# CorrienteTestMaquina.net
KiCad netlist of a schematic drawn in EAGLE
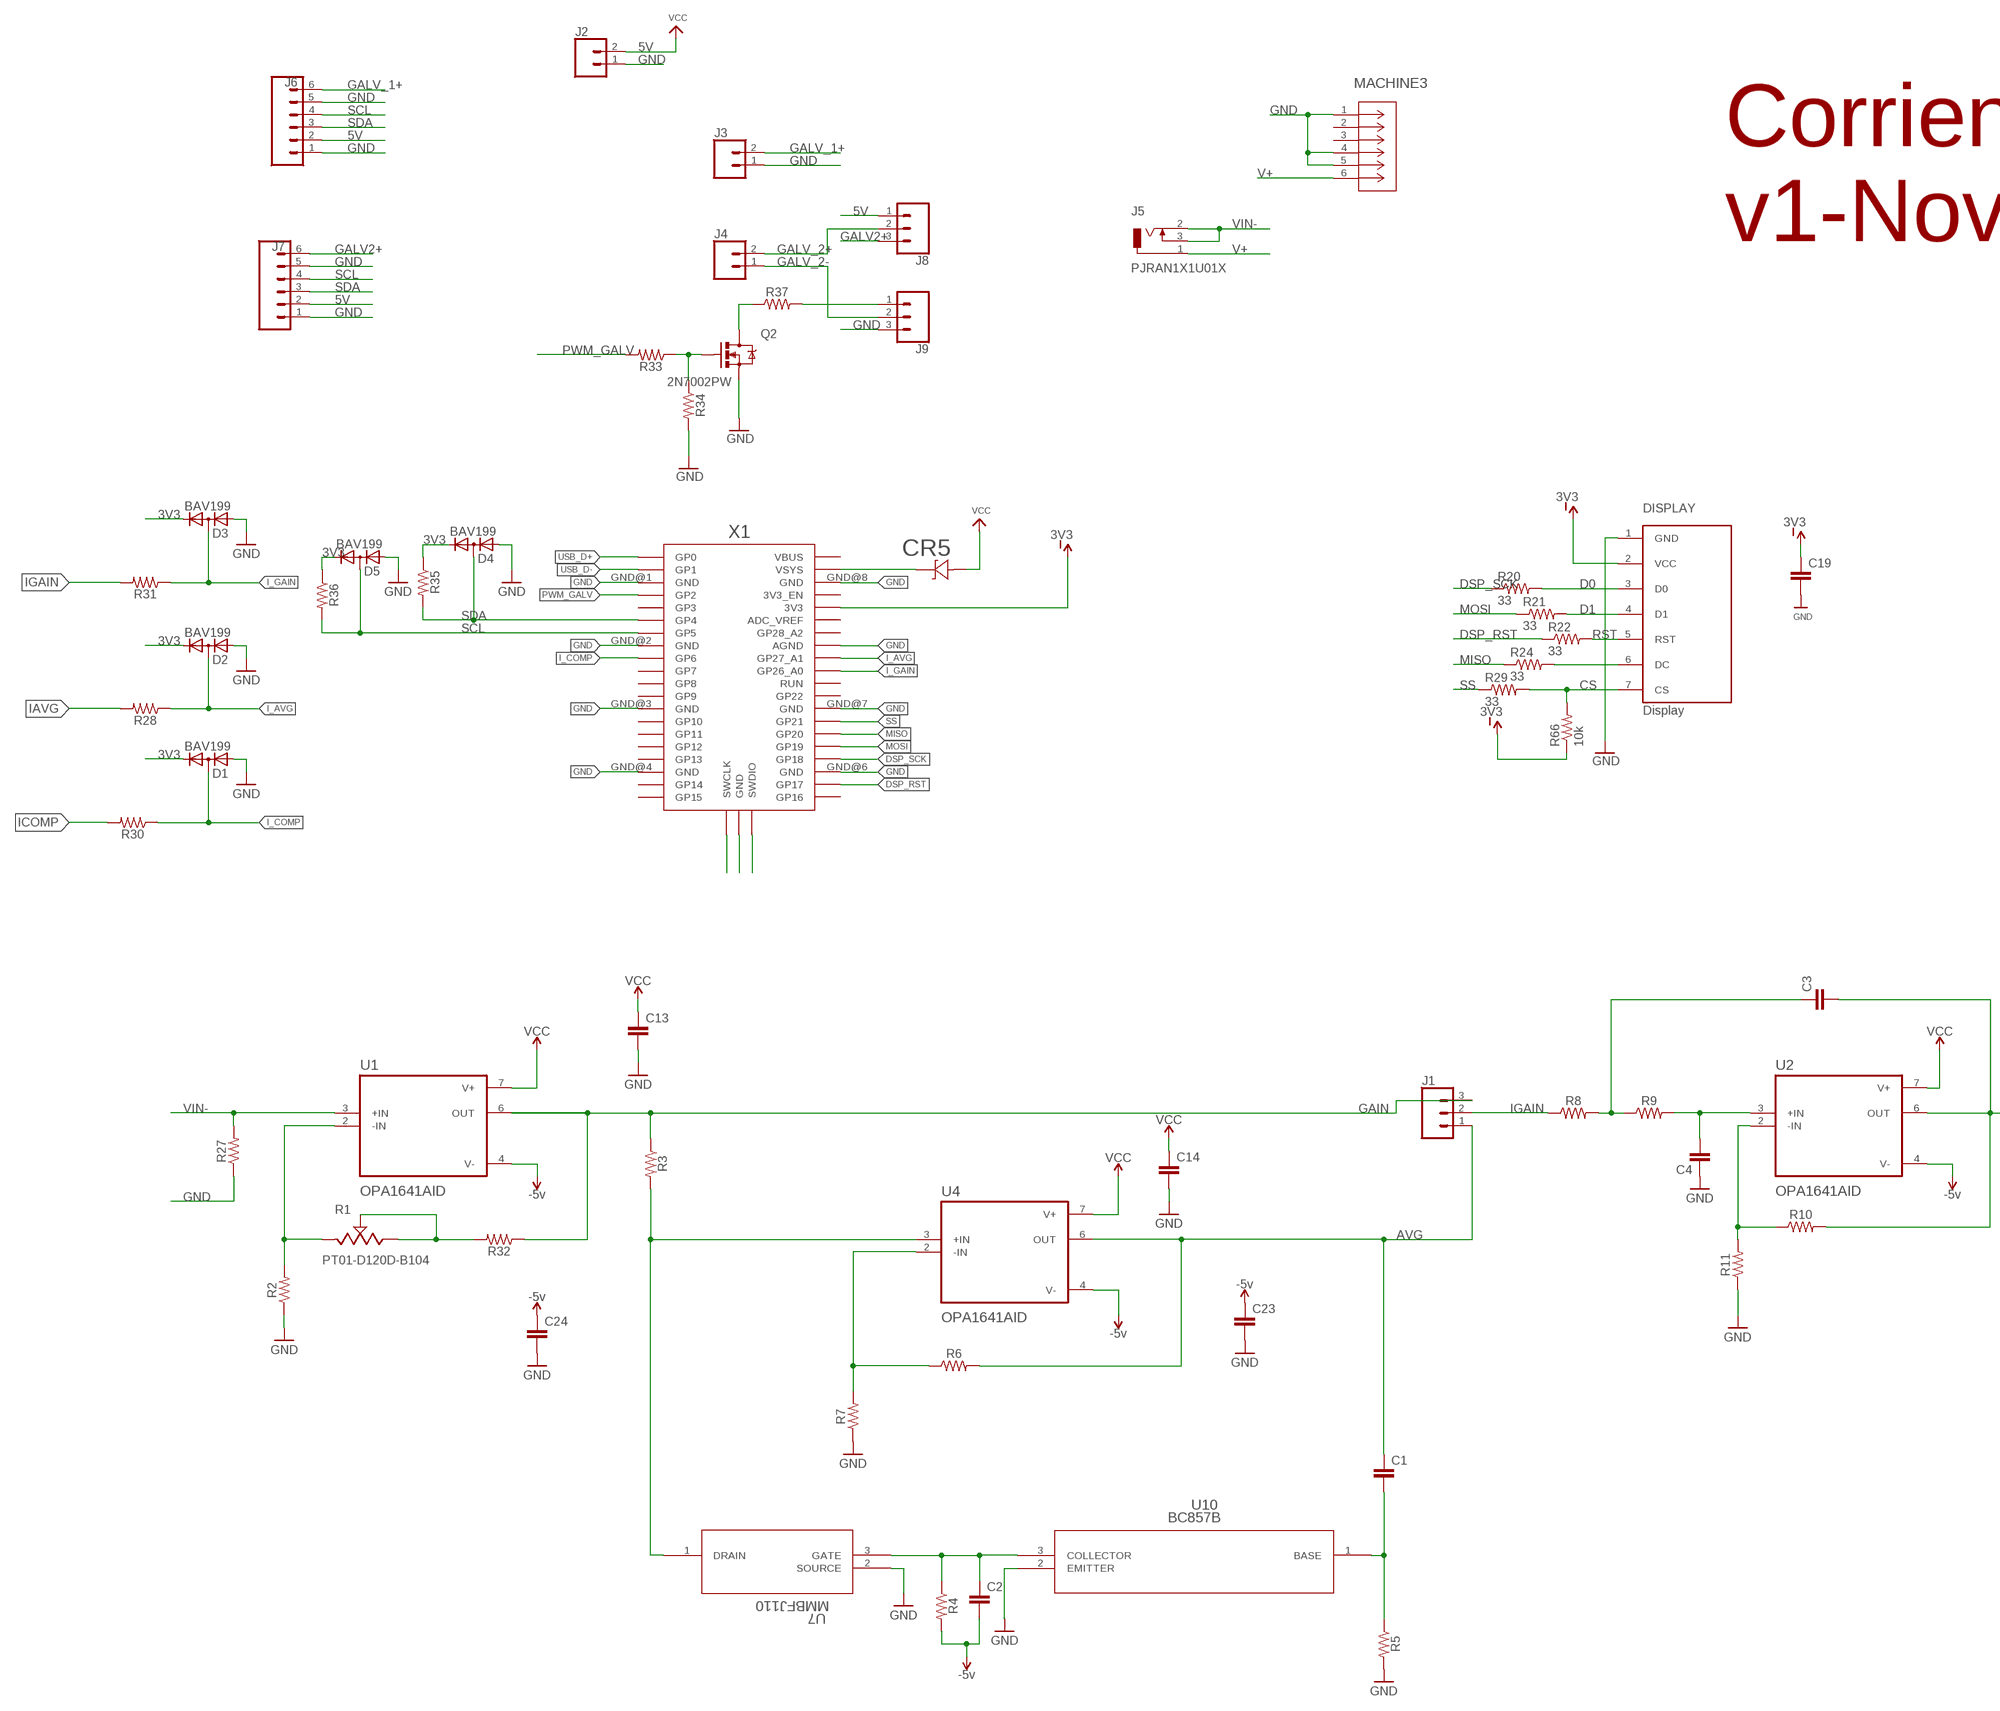
[diagram p0: schematic, sheet 1, part 1 of 2]
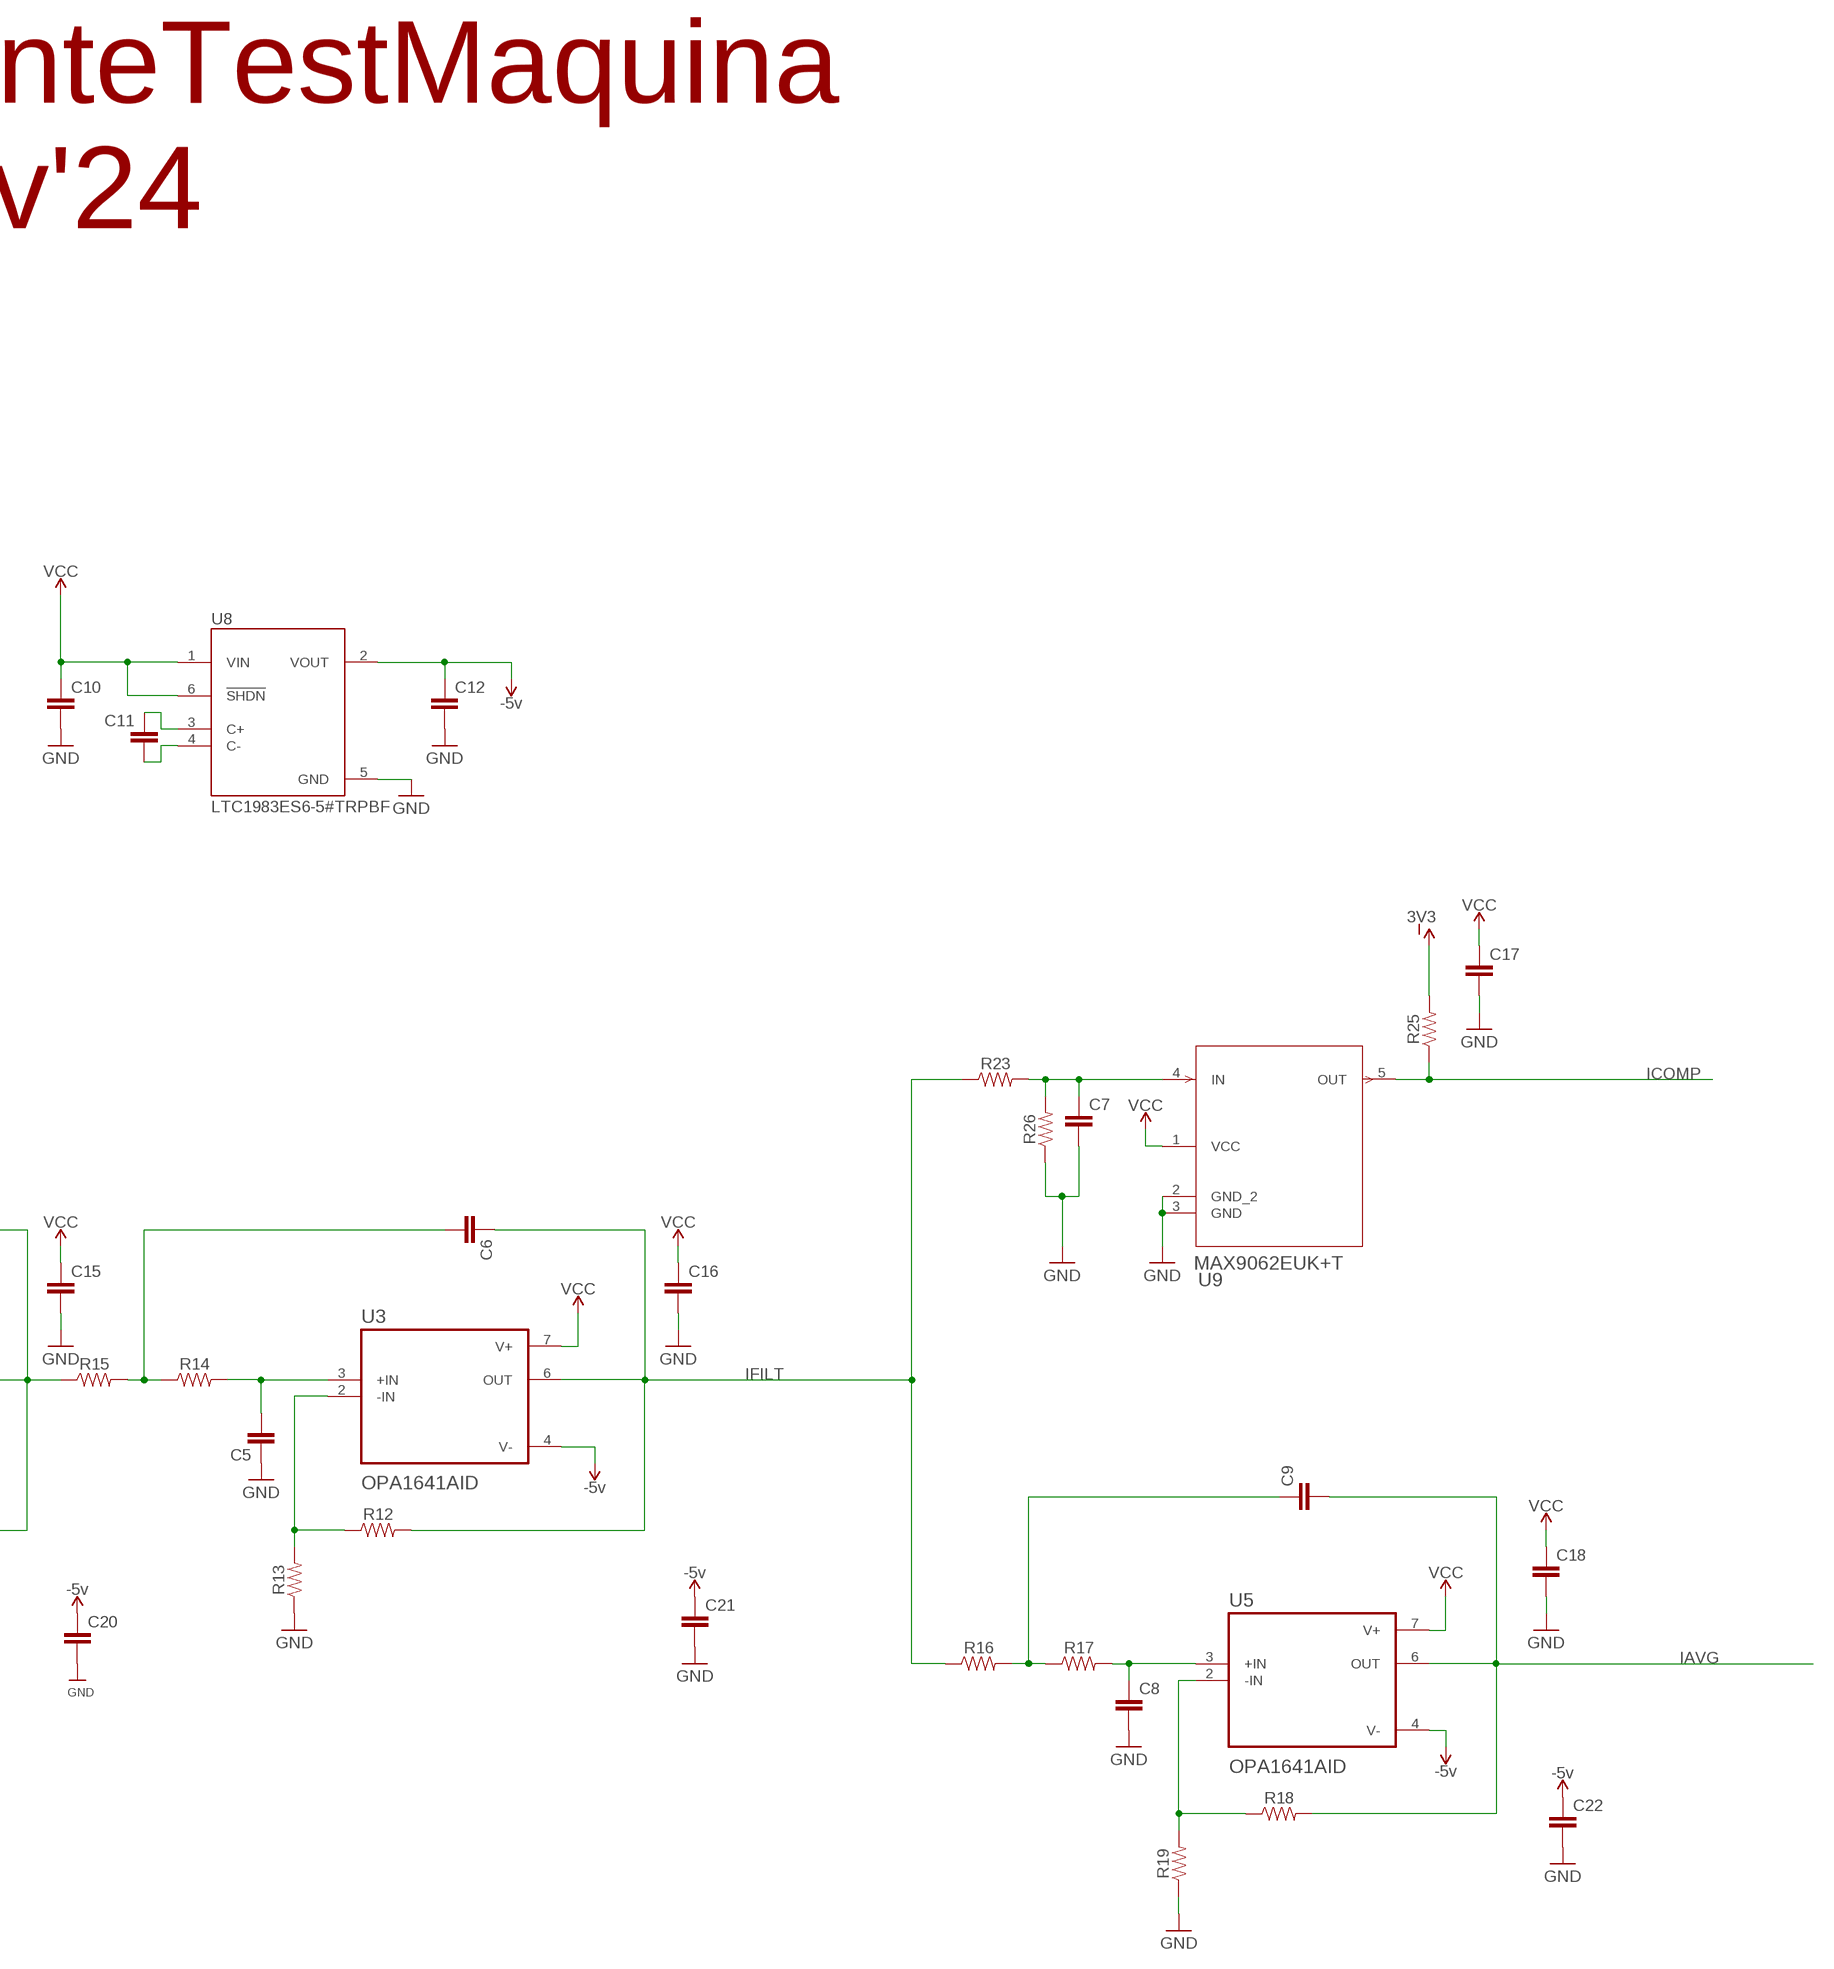
[diagram p1: schematic, sheet 1, part 2 of 2]

(export (version "E")
  (design (tool "Eeschema 10.0.6"))
  (components
    (comp (ref "C1")
      (value "CAP0805")
      (footprint "eagle-import:0805")
      (libsource (lib "eagle-import") (part "CAP0805"))
    )
    (comp (ref "C2")
      (value "CAP0805")
      (footprint "eagle-import:0805")
      (libsource (lib "eagle-import") (part "CAP0805"))
    )
    (comp (ref "C3")
      (value "CAP0805")
      (footprint "eagle-import:0805")
      (libsource (lib "eagle-import") (part "CAP0805"))
    )
    (comp (ref "C4")
      (value "CAP0805")
      (footprint "eagle-import:0805")
      (libsource (lib "eagle-import") (part "CAP0805"))
    )
    (comp (ref "C5")
      (value "CAP0805")
      (footprint "eagle-import:0805")
      (libsource (lib "eagle-import") (part "CAP0805"))
    )
    (comp (ref "C6")
      (value "CAP0805")
      (footprint "eagle-import:0805")
      (libsource (lib "eagle-import") (part "CAP0805"))
    )
    (comp (ref "C7")
      (value "CAP0805")
      (footprint "eagle-import:0805")
      (libsource (lib "eagle-import") (part "CAP0805"))
    )
    (comp (ref "C8")
      (value "CAP0805")
      (footprint "eagle-import:0805")
      (libsource (lib "eagle-import") (part "CAP0805"))
    )
    (comp (ref "C9")
      (value "CAP0805")
      (footprint "eagle-import:0805")
      (libsource (lib "eagle-import") (part "CAP0805"))
    )
    (comp (ref "C10")
      (value "CAP0805")
      (footprint "eagle-import:0805")
      (libsource (lib "eagle-import") (part "CAP0805"))
    )
    (comp (ref "C11")
      (value "CAP0805")
      (footprint "eagle-import:0805")
      (libsource (lib "eagle-import") (part "CAP0805"))
    )
    (comp (ref "C12")
      (value "CAP0805")
      (footprint "eagle-import:0805")
      (libsource (lib "eagle-import") (part "CAP0805"))
    )
    (comp (ref "C13")
      (value "CAP0805")
      (footprint "eagle-import:0805")
      (libsource (lib "eagle-import") (part "CAP0805"))
    )
    (comp (ref "C14")
      (value "CAP0805")
      (footprint "eagle-import:0805")
      (libsource (lib "eagle-import") (part "CAP0805"))
    )
    (comp (ref "C15")
      (value "CAP0805")
      (footprint "eagle-import:0805")
      (libsource (lib "eagle-import") (part "CAP0805"))
    )
    (comp (ref "C16")
      (value "CAP0805")
      (footprint "eagle-import:0805")
      (libsource (lib "eagle-import") (part "CAP0805"))
    )
    (comp (ref "C17")
      (value "CAP0805")
      (footprint "eagle-import:0805")
      (libsource (lib "eagle-import") (part "CAP0805"))
    )
    (comp (ref "C18")
      (value "CAP0805")
      (footprint "eagle-import:0805")
      (libsource (lib "eagle-import") (part "CAP0805"))
    )
    (comp (ref "C19")
      (value "CAP0805")
      (footprint "eagle-import:0805")
      (libsource (lib "eagle-import") (part "CAP0805"))
    )
    (comp (ref "C20")
      (value "CAP0805")
      (footprint "eagle-import:0805")
      (libsource (lib "eagle-import") (part "CAP0805"))
    )
    (comp (ref "C21")
      (value "CAP0805")
      (footprint "eagle-import:0805")
      (libsource (lib "eagle-import") (part "CAP0805"))
    )
    (comp (ref "C22")
      (value "CAP0805")
      (footprint "eagle-import:0805")
      (libsource (lib "eagle-import") (part "CAP0805"))
    )
    (comp (ref "C23")
      (value "CAP0805")
      (footprint "eagle-import:0805")
      (libsource (lib "eagle-import") (part "CAP0805"))
    )
    (comp (ref "C24")
      (value "CAP0805")
      (footprint "eagle-import:0805")
      (libsource (lib "eagle-import") (part "CAP0805"))
    )
    (comp (ref "CR5")
      (value "STPS1L40U")
      (footprint "eagle-import:SMB_STM")
      (fields (field (name "COPYRIGHT") "Copyright (C) 2024 Ultra Librarian. All rights reserved."))
      (libsource (lib "eagle-import") (part "STPS1L40U"))
    )
    (comp (ref "D1")
      (value "BAV199")
      (footprint "eagle-import:SOT23")
      (libsource (lib "eagle-import") (part "BAV199"))
    )
    (comp (ref "D2")
      (value "BAV199")
      (footprint "eagle-import:SOT23")
      (libsource (lib "eagle-import") (part "BAV199"))
    )
    (comp (ref "D3")
      (value "BAV199")
      (footprint "eagle-import:SOT23")
      (libsource (lib "eagle-import") (part "BAV199"))
    )
    (comp (ref "D4")
      (value "BAV199")
      (footprint "eagle-import:SOT23")
      (libsource (lib "eagle-import") (part "BAV199"))
    )
    (comp (ref "D5")
      (value "BAV199")
      (footprint "eagle-import:SOT23")
      (libsource (lib "eagle-import") (part "BAV199"))
    )
    (comp (ref "DISPLAY")
      (value "Display")
      (footprint "eagle-import:OLED_LCD")
      (libsource (lib "eagle-import") (part "OLED_LCD"))
    )
    (comp (ref "J1")
      (value "CONN_03")
      (footprint "eagle-import:1X03")
      (libsource (lib "eagle-import") (part "CONN_03"))
    )
    (comp (ref "J2")
      (value "CONN_02")
      (footprint "eagle-import:1X02")
      (libsource (lib "eagle-import") (part "CONN_02"))
    )
    (comp (ref "J3")
      (value "CONN_02")
      (footprint "eagle-import:1X02")
      (libsource (lib "eagle-import") (part "CONN_02"))
    )
    (comp (ref "J4")
      (value "CONN_02")
      (footprint "eagle-import:1X02")
      (libsource (lib "eagle-import") (part "CONN_02"))
    )
    (comp (ref "J5")
      (value "PJRAN1X1U01X")
      (footprint "eagle-import:PJRAN1X1U01X")
      (fields
        (field (name "DIGIKEY_PART_NUMBER") "PJRAN1X1U01X-ND")
        (field (name "MANUFACTURER") "Switchcraft Inc.")
        (field (name "CREATED_BY") "PCBLayout.com")
      )
      (libsource (lib "eagle-import") (part "PJRAN1X1U01X"))
    )
    (comp (ref "J6")
      (value "CONN_06SILK_FEMALE_PTH")
      (footprint "eagle-import:1X06")
      (libsource (lib "eagle-import") (part "CONN_06SILK_FEMALE_PTH"))
    )
    (comp (ref "J7")
      (value "CONN_06SILK_FEMALE_PTH")
      (footprint "eagle-import:1X06")
      (libsource (lib "eagle-import") (part "CONN_06SILK_FEMALE_PTH"))
    )
    (comp (ref "J8")
      (value "CONN_03")
      (footprint "eagle-import:1X03")
      (libsource (lib "eagle-import") (part "CONN_03"))
    )
    (comp (ref "J9")
      (value "CONN_03")
      (footprint "eagle-import:1X03")
      (libsource (lib "eagle-import") (part "CONN_03"))
    )
    (comp (ref "MACHINE3")
      (value "ACJS-MHDR")
      (footprint "eagle-import:CONN_MHDR_AMP")
      (fields (field (name "COPYRIGHT") "Copyright (C) 2018 Accelerated Designs. All rights reserved"))
      (libsource (lib "eagle-import") (part "ACJS-MHDR"))
    )
    (comp (ref "Q2")
      (value "2N7002PW")
      (footprint "eagle-import:SOT323")
      (libsource (lib "eagle-import") (part "MOSFET-NCHANNEL2N7002PW"))
    )
    (comp (ref "R1")
      (value "PT01-D120D-B104")
      (footprint "eagle-import:TRIM_PT01-D120D-B104")
      (fields (field (name "MANUFACTURER") "CUI Devices"))
      (libsource (lib "eagle-import") (part "PT01-D120D-B104"))
    )
    (comp (ref "R2")
      (value "RESISTOR0805")
      (footprint "eagle-import:0805")
      (libsource (lib "eagle-import") (part "RESISTOR0805"))
    )
    (comp (ref "R3")
      (value "RESISTOR0805")
      (footprint "eagle-import:0805")
      (libsource (lib "eagle-import") (part "RESISTOR0805"))
    )
    (comp (ref "R4")
      (value "RESISTOR0805")
      (footprint "eagle-import:0805")
      (libsource (lib "eagle-import") (part "RESISTOR0805"))
    )
    (comp (ref "R5")
      (value "RESISTOR0805")
      (footprint "eagle-import:0805")
      (libsource (lib "eagle-import") (part "RESISTOR0805"))
    )
    (comp (ref "R6")
      (value "RESISTOR0805")
      (footprint "eagle-import:0805")
      (libsource (lib "eagle-import") (part "RESISTOR0805"))
    )
    (comp (ref "R7")
      (value "RESISTOR0805")
      (footprint "eagle-import:0805")
      (libsource (lib "eagle-import") (part "RESISTOR0805"))
    )
    (comp (ref "R8")
      (value "RESISTOR0805")
      (footprint "eagle-import:0805")
      (libsource (lib "eagle-import") (part "RESISTOR0805"))
    )
    (comp (ref "R9")
      (value "RESISTOR0805")
      (footprint "eagle-import:0805")
      (libsource (lib "eagle-import") (part "RESISTOR0805"))
    )
    (comp (ref "R10")
      (value "RESISTOR0805")
      (footprint "eagle-import:0805")
      (libsource (lib "eagle-import") (part "RESISTOR0805"))
    )
    (comp (ref "R11")
      (value "RESISTOR0805")
      (footprint "eagle-import:0805")
      (libsource (lib "eagle-import") (part "RESISTOR0805"))
    )
    (comp (ref "R12")
      (value "RESISTOR0805")
      (footprint "eagle-import:0805")
      (libsource (lib "eagle-import") (part "RESISTOR0805"))
    )
    (comp (ref "R13")
      (value "RESISTOR0805")
      (footprint "eagle-import:0805")
      (libsource (lib "eagle-import") (part "RESISTOR0805"))
    )
    (comp (ref "R14")
      (value "RESISTOR0805")
      (footprint "eagle-import:0805")
      (libsource (lib "eagle-import") (part "RESISTOR0805"))
    )
    (comp (ref "R15")
      (value "RESISTOR0805")
      (footprint "eagle-import:0805")
      (libsource (lib "eagle-import") (part "RESISTOR0805"))
    )
    (comp (ref "R16")
      (value "RESISTOR0805")
      (footprint "eagle-import:0805")
      (libsource (lib "eagle-import") (part "RESISTOR0805"))
    )
    (comp (ref "R17")
      (value "RESISTOR0805")
      (footprint "eagle-import:0805")
      (libsource (lib "eagle-import") (part "RESISTOR0805"))
    )
    (comp (ref "R18")
      (value "RESISTOR0805")
      (footprint "eagle-import:0805")
      (libsource (lib "eagle-import") (part "RESISTOR0805"))
    )
    (comp (ref "R19")
      (value "RESISTOR0805")
      (footprint "eagle-import:0805")
      (libsource (lib "eagle-import") (part "RESISTOR0805"))
    )
    (comp (ref "R20")
      (value "33")
      (footprint "eagle-import:0805")
      (libsource (lib "eagle-import") (part "RESISTOR0805"))
    )
    (comp (ref "R21")
      (value "33")
      (footprint "eagle-import:0805")
      (libsource (lib "eagle-import") (part "RESISTOR0805"))
    )
    (comp (ref "R22")
      (value "33")
      (footprint "eagle-import:0805")
      (libsource (lib "eagle-import") (part "RESISTOR0805"))
    )
    (comp (ref "R23")
      (value "RESISTOR0805")
      (footprint "eagle-import:0805")
      (libsource (lib "eagle-import") (part "RESISTOR0805"))
    )
    (comp (ref "R24")
      (value "33")
      (footprint "eagle-import:0805")
      (libsource (lib "eagle-import") (part "RESISTOR0805"))
    )
    (comp (ref "R25")
      (value "RESISTOR0805")
      (footprint "eagle-import:0805")
      (libsource (lib "eagle-import") (part "RESISTOR0805"))
    )
    (comp (ref "R26")
      (value "RESISTOR0805")
      (footprint "eagle-import:0805")
      (libsource (lib "eagle-import") (part "RESISTOR0805"))
    )
    (comp (ref "R27")
      (value "RESISTOR1206")
      (footprint "eagle-import:1206")
      (libsource (lib "eagle-import") (part "RESISTOR1206"))
    )
    (comp (ref "R28")
      (value "RESISTOR0805")
      (footprint "eagle-import:0805")
      (libsource (lib "eagle-import") (part "RESISTOR0805"))
    )
    (comp (ref "R29")
      (value "33")
      (footprint "eagle-import:0805")
      (libsource (lib "eagle-import") (part "RESISTOR0805"))
    )
    (comp (ref "R30")
      (value "RESISTOR0805")
      (footprint "eagle-import:0805")
      (libsource (lib "eagle-import") (part "RESISTOR0805"))
    )
    (comp (ref "R31")
      (value "RESISTOR0805")
      (footprint "eagle-import:0805")
      (libsource (lib "eagle-import") (part "RESISTOR0805"))
    )
    (comp (ref "R32")
      (value "RESISTOR0805")
      (footprint "eagle-import:0805")
      (libsource (lib "eagle-import") (part "RESISTOR0805"))
    )
    (comp (ref "R33")
      (value "RESISTOR0805")
      (footprint "eagle-import:0805")
      (libsource (lib "eagle-import") (part "RESISTOR0805"))
    )
    (comp (ref "R34")
      (value "RESISTOR0805")
      (footprint "eagle-import:0805")
      (libsource (lib "eagle-import") (part "RESISTOR0805"))
    )
    (comp (ref "R35")
      (value "RESISTOR0805")
      (footprint "eagle-import:0805")
      (libsource (lib "eagle-import") (part "RESISTOR0805"))
    )
    (comp (ref "R36")
      (value "RESISTOR0805")
      (footprint "eagle-import:0805")
      (libsource (lib "eagle-import") (part "RESISTOR0805"))
    )
    (comp (ref "R37")
      (value "RESISTOR0805")
      (footprint "eagle-import:0805")
      (libsource (lib "eagle-import") (part "RESISTOR0805"))
    )
    (comp (ref "R66")
      (value "10k")
      (footprint "eagle-import:0805")
      (libsource (lib "eagle-import") (part "RESISTOR0805"))
    )
    (comp (ref "U1")
      (value "OPA1641AID")
      (footprint "eagle-import:SOIC127P599X175-8N")
      (libsource (lib "eagle-import") (part "OPA1641AID"))
    )
    (comp (ref "U2")
      (value "OPA1641AID")
      (footprint "eagle-import:SOIC127P599X175-8N")
      (libsource (lib "eagle-import") (part "OPA1641AID"))
    )
    (comp (ref "U3")
      (value "OPA1641AID")
      (footprint "eagle-import:SOIC127P599X175-8N")
      (libsource (lib "eagle-import") (part "OPA1641AID"))
    )
    (comp (ref "U4")
      (value "OPA1641AID")
      (footprint "eagle-import:SOIC127P599X175-8N")
      (libsource (lib "eagle-import") (part "OPA1641AID"))
    )
    (comp (ref "U5")
      (value "OPA1641AID")
      (footprint "eagle-import:SOIC127P599X175-8N")
      (libsource (lib "eagle-import") (part "OPA1641AID"))
    )
    (comp (ref "U7")
      (value "MMBFJ110")
      (footprint "eagle-import:SSOT3_3X1P5_ONS")
      (fields (field (name "COPYRIGHT") "Copyright (C) 2024 Ultra Librarian. All rights reserved."))
      (libsource (lib "eagle-import") (part "MMBFJ110"))
    )
    (comp (ref "U8")
      (value "LTC1983ES6-5#TRPBF")
      (footprint "eagle-import:SOT95P280X100-6N")
      (fields (field (name "MANUFACTURER") "LINEAR TECHNOLOGY"))
      (libsource (lib "eagle-import") (part "LTC1983ES6-5#TRPBF"))
    )
    (comp (ref "U9")
      (value "MAX9062EUK+T")
      (footprint "eagle-import:21-0057F_MXM")
      (libsource (lib "eagle-import") (part "MAX9062EUK+T"))
    )
    (comp (ref "U10")
      (value "BC857B")
      (footprint "eagle-import:SOT23_NXP")
      (fields (field (name "COPYRIGHT") "Copyright (C) 2024 Ultra Librarian. All rights reserved."))
      (libsource (lib "eagle-import") (part "BC857B"))
    )
    (comp (ref "X1")
      (value "RPI_PICO_IG-TH")
      (footprint "eagle-import:RPI_PICO_TH")
      (libsource (lib "eagle-import") (part "RPI_PICO_IG-TH"))
    )
  )
  (nets
    (net (code "1") (name "-5v") (class "Default")
      (node (ref "C12") (pin "1") (pinfunction "1_1") (pintype "passive"))
      (node (ref "C2") (pin "2") (pinfunction "2_2") (pintype "passive"))
      (node (ref "C20") (pin "1") (pinfunction "1_1") (pintype "passive"))
      (node (ref "C21") (pin "1") (pinfunction "1_1") (pintype "passive"))
      (node (ref "C22") (pin "1") (pinfunction "1_1") (pintype "passive"))
      (node (ref "C23") (pin "1") (pinfunction "1_1") (pintype "passive"))
      (node (ref "C24") (pin "1") (pinfunction "1_1") (pintype "passive"))
      (node (ref "R4") (pin "2") (pinfunction "2_2") (pintype "passive"))
      (node (ref "U1") (pin "4") (pinfunction "V-_4") (pintype "power_in"))
      (node (ref "U2") (pin "4") (pinfunction "V-_4") (pintype "power_in"))
      (node (ref "U3") (pin "4") (pinfunction "V-_4") (pintype "power_in"))
      (node (ref "U4") (pin "4") (pinfunction "V-_4") (pintype "power_in"))
      (node (ref "U5") (pin "4") (pinfunction "V-_4") (pintype "power_in"))
      (node (ref "U8") (pin "2") (pinfunction "VOUT_2") (pintype "output"))
    )
    (net (code "2") (name "/AVG") (class "Default")
      (node (ref "C1") (pin "1") (pinfunction "1_1") (pintype "passive"))
      (node (ref "J1") (pin "1") (pinfunction "1_1") (pintype "passive"))
      (node (ref "R6") (pin "2") (pinfunction "2_2") (pintype "passive"))
      (node (ref "U4") (pin "6") (pinfunction "OUT_6") (pintype "output"))
    )
    (net (code "3") (name "/CS") (class "Default")
      (node (ref "DISPLAY") (pin "7") (pinfunction "CS_7") (pintype "bidirectional"))
      (node (ref "R29") (pin "2") (pinfunction "2_2") (pintype "passive"))
      (node (ref "R66") (pin "2") (pinfunction "2_2") (pintype "passive"))
    )
    (net (code "4") (name "/D0") (class "Default")
      (node (ref "DISPLAY") (pin "3") (pinfunction "D0_3") (pintype "bidirectional"))
      (node (ref "R20") (pin "2") (pinfunction "2_2") (pintype "passive"))
    )
    (net (code "5") (name "/D1") (class "Default")
      (node (ref "DISPLAY") (pin "4") (pinfunction "D1_4") (pintype "bidirectional"))
      (node (ref "R21") (pin "2") (pinfunction "2_2") (pintype "passive"))
    )
    (net (code "6") (name "/GAIN") (class "Default")
      (node (ref "J1") (pin "3") (pinfunction "3_3") (pintype "passive"))
      (node (ref "R3") (pin "1") (pinfunction "1_1") (pintype "passive"))
      (node (ref "R32") (pin "1") (pinfunction "1_1") (pintype "passive"))
      (node (ref "U1") (pin "6") (pinfunction "OUT_6") (pintype "output"))
    )
    (net (code "7") (name "/GALV2+") (class "Default")
      (node (ref "J7") (pin "6") (pinfunction "6_6") (pintype "passive"))
      (node (ref "J8") (pin "3") (pinfunction "3_3") (pintype "passive"))
    )
    (net (code "8") (name "/GALV_1+") (class "Default")
      (node (ref "J3") (pin "2") (pinfunction "2_2") (pintype "passive"))
      (node (ref "J6") (pin "6") (pinfunction "6_6") (pintype "passive"))
    )
    (net (code "9") (name "/GALV_2+") (class "Default")
      (node (ref "J4") (pin "2") (pinfunction "2_2") (pintype "passive"))
      (node (ref "J8") (pin "2") (pinfunction "2_2") (pintype "passive"))
    )
    (net (code "10") (name "/GALV_2-") (class "Default")
      (node (ref "J4") (pin "1") (pinfunction "1_1") (pintype "passive"))
      (node (ref "J9") (pin "2") (pinfunction "2_2") (pintype "passive"))
    )
    (net (code "11") (name "/IFILT") (class "Default")
      (node (ref "C6") (pin "1") (pinfunction "1_1") (pintype "passive"))
      (node (ref "R12") (pin "2") (pinfunction "2_2") (pintype "passive"))
      (node (ref "R16") (pin "1") (pinfunction "1_1") (pintype "passive"))
      (node (ref "R23") (pin "1") (pinfunction "1_1") (pintype "passive"))
      (node (ref "U3") (pin "6") (pinfunction "OUT_6") (pintype "output"))
    )
    (net (code "12") (name "/RST") (class "Default")
      (node (ref "DISPLAY") (pin "5") (pinfunction "RST_5") (pintype "bidirectional"))
      (node (ref "R22") (pin "2") (pinfunction "2_2") (pintype "passive"))
    )
    (net (code "13") (name "/SCL") (class "Default")
      (node (ref "D5") (pin "3") (pinfunction "AC_3") (pintype "passive"))
      (node (ref "J6") (pin "4") (pinfunction "4_4") (pintype "passive"))
      (node (ref "J7") (pin "4") (pinfunction "4_4") (pintype "passive"))
      (node (ref "R36") (pin "2") (pinfunction "2_2") (pintype "passive"))
      (node (ref "X1") (pin "GP5") (pinfunction "GP5_GP5") (pintype "bidirectional"))
    )
    (net (code "14") (name "/SDA") (class "Default")
      (node (ref "D4") (pin "3") (pinfunction "AC_3") (pintype "passive"))
      (node (ref "J6") (pin "3") (pinfunction "3_3") (pintype "passive"))
      (node (ref "J7") (pin "3") (pinfunction "3_3") (pintype "passive"))
      (node (ref "R35") (pin "2") (pinfunction "2_2") (pintype "passive"))
      (node (ref "X1") (pin "GP4") (pinfunction "GP4_GP4") (pintype "bidirectional"))
    )
    (net (code "15") (name "/V+") (class "Default")
      (node (ref "J5") (pin "1") (pinfunction "1_1") (pintype "passive"))
      (node (ref "MACHINE3") (pin "6") (pinfunction "6_6") (pintype "passive"))
    )
    (net (code "16") (name "/VIN-") (class "Default")
      (node (ref "J5") (pin "2") (pinfunction "2_2") (pintype "passive"))
      (node (ref "J5") (pin "3") (pinfunction "3_3") (pintype "passive"))
      (node (ref "R27") (pin "2") (pinfunction "2_2") (pintype "passive"))
      (node (ref "U1") (pin "3") (pinfunction "+IN_3") (pintype "input"))
    )
    (net (code "17") (name "3V3") (class "Default")
      (node (ref "C19") (pin "1") (pinfunction "1_1") (pintype "passive"))
      (node (ref "D1") (pin "2") (pinfunction "C_2") (pintype "passive"))
      (node (ref "D2") (pin "2") (pinfunction "C_2") (pintype "passive"))
      (node (ref "D3") (pin "2") (pinfunction "C_2") (pintype "passive"))
      (node (ref "D4") (pin "2") (pinfunction "C_2") (pintype "passive"))
      (node (ref "D5") (pin "2") (pinfunction "C_2") (pintype "passive"))
      (node (ref "DISPLAY") (pin "2") (pinfunction "VCC_2") (pintype "bidirectional"))
      (node (ref "R25") (pin "2") (pinfunction "2_2") (pintype "passive"))
      (node (ref "R35") (pin "1") (pinfunction "1_1") (pintype "passive"))
      (node (ref "R36") (pin "1") (pinfunction "1_1") (pintype "passive"))
      (node (ref "R66") (pin "1") (pinfunction "1_1") (pintype "passive"))
      (node (ref "X1") (pin "3V3") (pinfunction "3V3_3V3") (pintype "bidirectional"))
    )
    (net (code "18") (name "DSP_RST") (class "Default")
      (node (ref "R22") (pin "1") (pinfunction "1_1") (pintype "passive"))
      (node (ref "X1") (pin "GP17") (pinfunction "GP17_GP17") (pintype "bidirectional"))
    )
    (net (code "19") (name "DSP_SCK") (class "Default")
      (node (ref "R20") (pin "1") (pinfunction "1_1") (pintype "passive"))
      (node (ref "X1") (pin "GP18") (pinfunction "GP18_GP18") (pintype "bidirectional"))
    )
    (net (code "20") (name "GND") (class "Default")
      (node (ref "C10") (pin "2") (pinfunction "2_2") (pintype "passive"))
      (node (ref "C12") (pin "2") (pinfunction "2_2") (pintype "passive"))
      (node (ref "C13") (pin "2") (pinfunction "2_2") (pintype "passive"))
      (node (ref "C14") (pin "2") (pinfunction "2_2") (pintype "passive"))
      (node (ref "C15") (pin "2") (pinfunction "2_2") (pintype "passive"))
      (node (ref "C16") (pin "2") (pinfunction "2_2") (pintype "passive"))
      (node (ref "C17") (pin "2") (pinfunction "2_2") (pintype "passive"))
      (node (ref "C18") (pin "2") (pinfunction "2_2") (pintype "passive"))
      (node (ref "C19") (pin "2") (pinfunction "2_2") (pintype "passive"))
      (node (ref "C20") (pin "2") (pinfunction "2_2") (pintype "passive"))
      (node (ref "C21") (pin "2") (pinfunction "2_2") (pintype "passive"))
      (node (ref "C22") (pin "2") (pinfunction "2_2") (pintype "passive"))
      (node (ref "C23") (pin "2") (pinfunction "2_2") (pintype "passive"))
      (node (ref "C24") (pin "2") (pinfunction "2_2") (pintype "passive"))
      (node (ref "C4") (pin "1") (pinfunction "1_1") (pintype "passive"))
      (node (ref "C5") (pin "1") (pinfunction "1_1") (pintype "passive"))
      (node (ref "C7") (pin "2") (pinfunction "2_2") (pintype "passive"))
      (node (ref "C8") (pin "2") (pinfunction "2_2") (pintype "passive"))
      (node (ref "D1") (pin "1") (pinfunction "A_1") (pintype "passive"))
      (node (ref "D2") (pin "1") (pinfunction "A_1") (pintype "passive"))
      (node (ref "D3") (pin "1") (pinfunction "A_1") (pintype "passive"))
      (node (ref "D4") (pin "1") (pinfunction "A_1") (pintype "passive"))
      (node (ref "D5") (pin "1") (pinfunction "A_1") (pintype "passive"))
      (node (ref "DISPLAY") (pin "1") (pinfunction "GND_1") (pintype "bidirectional"))
      (node (ref "J2") (pin "1") (pinfunction "1_1") (pintype "passive"))
      (node (ref "J3") (pin "1") (pinfunction "1_1") (pintype "passive"))
      (node (ref "J6") (pin "1") (pinfunction "1_1") (pintype "passive"))
      (node (ref "J6") (pin "5") (pinfunction "5_5") (pintype "passive"))
      (node (ref "J7") (pin "1") (pinfunction "1_1") (pintype "passive"))
      (node (ref "J7") (pin "5") (pinfunction "5_5") (pintype "passive"))
      (node (ref "J9") (pin "3") (pinfunction "3_3") (pintype "passive"))
      (node (ref "MACHINE3") (pin "1") (pinfunction "1_1") (pintype "passive"))
      (node (ref "MACHINE3") (pin "4") (pinfunction "4_4") (pintype "passive"))
      (node (ref "MACHINE3") (pin "5") (pinfunction "5_5") (pintype "passive"))
      (node (ref "Q2") (pin "2") (pinfunction "S_2") (pintype "passive"))
      (node (ref "R11") (pin "1") (pinfunction "1_1") (pintype "passive"))
      (node (ref "R13") (pin "1") (pinfunction "1_1") (pintype "passive"))
      (node (ref "R19") (pin "1") (pinfunction "1_1") (pintype "passive"))
      (node (ref "R2") (pin "1") (pinfunction "1_1") (pintype "passive"))
      (node (ref "R26") (pin "1") (pinfunction "1_1") (pintype "passive"))
      (node (ref "R27") (pin "1") (pinfunction "1_1") (pintype "passive"))
      (node (ref "R34") (pin "2") (pinfunction "2_2") (pintype "passive"))
      (node (ref "R5") (pin "2") (pinfunction "2_2") (pintype "passive"))
      (node (ref "R7") (pin "1") (pinfunction "1_1") (pintype "passive"))
      (node (ref "U10") (pin "2") (pinfunction "EMITTER_2") (pintype "passive"))
      (node (ref "U7") (pin "2") (pinfunction "SOURCE_2") (pintype "passive"))
      (node (ref "U8") (pin "5") (pinfunction "GND_5") (pintype "power_in"))
      (node (ref "U9") (pin "2") (pinfunction "GND_2_2") (pintype "power_in"))
      (node (ref "U9") (pin "3") (pinfunction "GND_3") (pintype "power_in"))
      (node (ref "X1") (pin "AGND") (pinfunction "AGND_AGND") (pintype "bidirectional"))
      (node (ref "X1") (pin "GND@1") (pinfunction "GND_GND@1") (pintype "bidirectional"))
      (node (ref "X1") (pin "GND@2") (pinfunction "GND_GND@2") (pintype "bidirectional"))
      (node (ref "X1") (pin "GND@3") (pinfunction "GND_GND@3") (pintype "bidirectional"))
      (node (ref "X1") (pin "GND@4") (pinfunction "GND_GND@4") (pintype "bidirectional"))
      (node (ref "X1") (pin "GND@6") (pinfunction "GND_GND@6") (pintype "bidirectional"))
      (node (ref "X1") (pin "GND@7") (pinfunction "GND_GND@7") (pintype "bidirectional"))
      (node (ref "X1") (pin "GND@8") (pinfunction "GND_GND@8") (pintype "bidirectional"))
    )
    (net (code "21") (name "IAVG") (class "Default")
      (node (ref "C9") (pin "2") (pinfunction "2_2") (pintype "passive"))
      (node (ref "R18") (pin "2") (pinfunction "2_2") (pintype "passive"))
      (node (ref "R28") (pin "2") (pinfunction "2_2") (pintype "passive"))
      (node (ref "U5") (pin "6") (pinfunction "OUT_6") (pintype "output"))
    )
    (net (code "22") (name "ICOMP") (class "Default")
      (node (ref "R25") (pin "1") (pinfunction "1_1") (pintype "passive"))
      (node (ref "R30") (pin "2") (pinfunction "2_2") (pintype "passive"))
      (node (ref "U9") (pin "5") (pinfunction "OUT_5") (pintype "output"))
    )
    (net (code "23") (name "IGAIN") (class "Default")
      (node (ref "J1") (pin "2") (pinfunction "2_2") (pintype "passive"))
      (node (ref "R31") (pin "2") (pinfunction "2_2") (pintype "passive"))
      (node (ref "R8") (pin "1") (pinfunction "1_1") (pintype "passive"))
    )
    (net (code "24") (name "I_AVG") (class "Default")
      (node (ref "D2") (pin "3") (pinfunction "AC_3") (pintype "passive"))
      (node (ref "R28") (pin "1") (pinfunction "1_1") (pintype "passive"))
      (node (ref "X1") (pin "GP27_A1") (pinfunction "GP27_A1_GP27_A1") (pintype "bidirectional"))
    )
    (net (code "25") (name "I_COMP") (class "Default")
      (node (ref "D1") (pin "3") (pinfunction "AC_3") (pintype "passive"))
      (node (ref "R30") (pin "1") (pinfunction "1_1") (pintype "passive"))
      (node (ref "X1") (pin "GP6") (pinfunction "GP6_GP6") (pintype "bidirectional"))
    )
    (net (code "26") (name "I_GAIN") (class "Default")
      (node (ref "D3") (pin "3") (pinfunction "AC_3") (pintype "passive"))
      (node (ref "R31") (pin "1") (pinfunction "1_1") (pintype "passive"))
      (node (ref "X1") (pin "GP26_A0") (pinfunction "GP26_A0_GP26_A0") (pintype "bidirectional"))
    )
    (net (code "27") (name "MISO") (class "Default")
      (node (ref "R24") (pin "1") (pinfunction "1_1") (pintype "passive"))
      (node (ref "X1") (pin "GP20") (pinfunction "GP20_GP20") (pintype "bidirectional"))
    )
    (net (code "28") (name "MOSI") (class "Default")
      (node (ref "R21") (pin "1") (pinfunction "1_1") (pintype "passive"))
      (node (ref "X1") (pin "GP19") (pinfunction "GP19_GP19") (pintype "bidirectional"))
    )
    (net (code "29") (name "Net-(C3-Pad1)") (class "Default")
      (node (ref "C3") (pin "1") (pinfunction "1_1") (pintype "passive"))
      (node (ref "R8") (pin "2") (pinfunction "2_2") (pintype "passive"))
      (node (ref "R9") (pin "1") (pinfunction "1_1") (pintype "passive"))
    )
    (net (code "30") (name "Net-(C6-Pad2)") (class "Default")
      (node (ref "C6") (pin "2") (pinfunction "2_2") (pintype "passive"))
      (node (ref "R14") (pin "1") (pinfunction "1_1") (pintype "passive"))
      (node (ref "R15") (pin "2") (pinfunction "2_2") (pintype "passive"))
    )
    (net (code "31") (name "Net-(C9-Pad1)") (class "Default")
      (node (ref "C9") (pin "1") (pinfunction "1_1") (pintype "passive"))
      (node (ref "R16") (pin "2") (pinfunction "2_2") (pintype "passive"))
      (node (ref "R17") (pin "1") (pinfunction "1_1") (pintype "passive"))
    )
    (net (code "32") (name "Net-(CR5-Pad2)") (class "Default")
      (node (ref "CR5") (pin "2") (pinfunction "2_2") (pintype "passive"))
      (node (ref "X1") (pin "VSYS") (pinfunction "VSYS_VSYS") (pintype "bidirectional"))
    )
    (net (code "33") (name "Net-(DISPLAY-DC)") (class "Default")
      (node (ref "DISPLAY") (pin "6") (pinfunction "DC_6") (pintype "bidirectional"))
      (node (ref "R24") (pin "2") (pinfunction "2_2") (pintype "passive"))
    )
    (net (code "34") (name "Net-(J9-Pad1)") (class "Default")
      (node (ref "J9") (pin "1") (pinfunction "1_1") (pintype "passive"))
      (node (ref "R37") (pin "2") (pinfunction "2_2") (pintype "passive"))
    )
    (net (code "35") (name "Net-(Q2-D)") (class "Default")
      (node (ref "Q2") (pin "3") (pinfunction "D_3") (pintype "passive"))
      (node (ref "R37") (pin "1") (pinfunction "1_1") (pintype "passive"))
    )
    (net (code "36") (name "Net-(Q2-G)") (class "Default")
      (node (ref "Q2") (pin "1") (pinfunction "G_1") (pintype "passive"))
      (node (ref "R33") (pin "1") (pinfunction "1_1") (pintype "passive"))
      (node (ref "R34") (pin "1") (pinfunction "1_1") (pintype "passive"))
    )
    (net (code "37") (name "Net-(R1-Pad2)") (class "Default")
      (node (ref "R1") (pin "2") (pinfunction "2_2") (pintype "passive"))
      (node (ref "R1") (pin "3") (pinfunction "3_3") (pintype "passive"))
      (node (ref "R32") (pin "2") (pinfunction "2_2") (pintype "passive"))
    )
    (net (code "38") (name "Net-(U1--IN)") (class "Default")
      (node (ref "R1") (pin "1") (pinfunction "1_1") (pintype "passive"))
      (node (ref "R2") (pin "2") (pinfunction "2_2") (pintype "passive"))
      (node (ref "U1") (pin "2") (pinfunction "-IN_2") (pintype "input"))
    )
    (net (code "39") (name "Net-(U2-+IN)") (class "Default")
      (node (ref "C4") (pin "2") (pinfunction "2_2") (pintype "passive"))
      (node (ref "R9") (pin "2") (pinfunction "2_2") (pintype "passive"))
      (node (ref "U2") (pin "3") (pinfunction "+IN_3") (pintype "input"))
    )
    (net (code "40") (name "Net-(U2--IN)") (class "Default")
      (node (ref "R10") (pin "1") (pinfunction "1_1") (pintype "passive"))
      (node (ref "R11") (pin "2") (pinfunction "2_2") (pintype "passive"))
      (node (ref "U2") (pin "2") (pinfunction "-IN_2") (pintype "input"))
    )
    (net (code "41") (name "Net-(U2-OUT)") (class "Default")
      (node (ref "C3") (pin "2") (pinfunction "2_2") (pintype "passive"))
      (node (ref "R10") (pin "2") (pinfunction "2_2") (pintype "passive"))
      (node (ref "R15") (pin "1") (pinfunction "1_1") (pintype "passive"))
      (node (ref "U2") (pin "6") (pinfunction "OUT_6") (pintype "output"))
    )
    (net (code "42") (name "Net-(U3-+IN)") (class "Default")
      (node (ref "C5") (pin "2") (pinfunction "2_2") (pintype "passive"))
      (node (ref "R14") (pin "2") (pinfunction "2_2") (pintype "passive"))
      (node (ref "U3") (pin "3") (pinfunction "+IN_3") (pintype "input"))
    )
    (net (code "43") (name "Net-(U3--IN)") (class "Default")
      (node (ref "R12") (pin "1") (pinfunction "1_1") (pintype "passive"))
      (node (ref "R13") (pin "2") (pinfunction "2_2") (pintype "passive"))
      (node (ref "U3") (pin "2") (pinfunction "-IN_2") (pintype "input"))
    )
    (net (code "44") (name "Net-(U4-+IN)") (class "Default")
      (node (ref "R3") (pin "2") (pinfunction "2_2") (pintype "passive"))
      (node (ref "U4") (pin "3") (pinfunction "+IN_3") (pintype "input"))
      (node (ref "U7") (pin "1") (pinfunction "DRAIN_1") (pintype "passive"))
    )
    (net (code "45") (name "Net-(U4--IN)") (class "Default")
      (node (ref "R6") (pin "1") (pinfunction "1_1") (pintype "passive"))
      (node (ref "R7") (pin "2") (pinfunction "2_2") (pintype "passive"))
      (node (ref "U4") (pin "2") (pinfunction "-IN_2") (pintype "input"))
    )
    (net (code "46") (name "Net-(U5-+IN)") (class "Default")
      (node (ref "C8") (pin "1") (pinfunction "1_1") (pintype "passive"))
      (node (ref "R17") (pin "2") (pinfunction "2_2") (pintype "passive"))
      (node (ref "U5") (pin "3") (pinfunction "+IN_3") (pintype "input"))
    )
    (net (code "47") (name "Net-(U5--IN)") (class "Default")
      (node (ref "R18") (pin "1") (pinfunction "1_1") (pintype "passive"))
      (node (ref "R19") (pin "2") (pinfunction "2_2") (pintype "passive"))
      (node (ref "U5") (pin "2") (pinfunction "-IN_2") (pintype "input"))
    )
    (net (code "48") (name "Net-(U8-C+)") (class "Default")
      (node (ref "C11") (pin "1") (pinfunction "1_1") (pintype "passive"))
      (node (ref "U8") (pin "3") (pinfunction "C+_3") (pintype "passive"))
    )
    (net (code "49") (name "Net-(U8-C-)") (class "Default")
      (node (ref "C11") (pin "2") (pinfunction "2_2") (pintype "passive"))
      (node (ref "U8") (pin "4") (pinfunction "C-_4") (pintype "passive"))
    )
    (net (code "50") (name "Net-(U9-IN)") (class "Default")
      (node (ref "C7") (pin "1") (pinfunction "1_1") (pintype "passive"))
      (node (ref "R23") (pin "2") (pinfunction "2_2") (pintype "passive"))
      (node (ref "R26") (pin "2") (pinfunction "2_2") (pintype "passive"))
      (node (ref "U9") (pin "4") (pinfunction "IN_4") (pintype "input"))
    )
    (net (code "51") (name "Net-(U10-BASE)") (class "Default")
      (node (ref "C1") (pin "2") (pinfunction "2_2") (pintype "passive"))
      (node (ref "R5") (pin "1") (pinfunction "1_1") (pintype "passive"))
      (node (ref "U10") (pin "1") (pinfunction "BASE_1") (pintype "passive"))
    )
    (net (code "52") (name "Net-(U10-COLLECTOR)") (class "Default")
      (node (ref "C2") (pin "1") (pinfunction "1_1") (pintype "passive"))
      (node (ref "R4") (pin "1") (pinfunction "1_1") (pintype "passive"))
      (node (ref "U10") (pin "3") (pinfunction "COLLECTOR_3") (pintype "passive"))
      (node (ref "U7") (pin "3") (pinfunction "GATE_3") (pintype "passive"))
    )
    (net (code "53") (name "PWM_GALV") (class "Default")
      (node (ref "R33") (pin "2") (pinfunction "2_2") (pintype "passive"))
      (node (ref "X1") (pin "GP2") (pinfunction "GP2_GP2") (pintype "bidirectional"))
    )
    (net (code "54") (name "SS") (class "Default")
      (node (ref "R29") (pin "1") (pinfunction "1_1") (pintype "passive"))
      (node (ref "X1") (pin "GP21") (pinfunction "GP21_GP21") (pintype "bidirectional"))
    )
    (net (code "55") (name "USB_D+") (class "Default")
      (node (ref "X1") (pin "GP0") (pinfunction "GP0_GP0") (pintype "bidirectional"))
    )
    (net (code "56") (name "USB_D-") (class "Default")
      (node (ref "X1") (pin "GP1") (pinfunction "GP1_GP1") (pintype "bidirectional"))
    )
    (net (code "57") (name "VCC") (class "Default")
      (node (ref "C10") (pin "1") (pinfunction "1_1") (pintype "passive"))
      (node (ref "C13") (pin "1") (pinfunction "1_1") (pintype "passive"))
      (node (ref "C14") (pin "1") (pinfunction "1_1") (pintype "passive"))
      (node (ref "C15") (pin "1") (pinfunction "1_1") (pintype "passive"))
      (node (ref "C16") (pin "1") (pinfunction "1_1") (pintype "passive"))
      (node (ref "C17") (pin "1") (pinfunction "1_1") (pintype "passive"))
      (node (ref "C18") (pin "1") (pinfunction "1_1") (pintype "passive"))
      (node (ref "CR5") (pin "1") (pinfunction "1_1") (pintype "passive"))
      (node (ref "J2") (pin "2") (pinfunction "2_2") (pintype "passive"))
      (node (ref "J6") (pin "2") (pinfunction "2_2") (pintype "passive"))
      (node (ref "J7") (pin "2") (pinfunction "2_2") (pintype "passive"))
      (node (ref "J8") (pin "1") (pinfunction "1_1") (pintype "passive"))
      (node (ref "U1") (pin "7") (pinfunction "V+_7") (pintype "power_in"))
      (node (ref "U2") (pin "7") (pinfunction "V+_7") (pintype "power_in"))
      (node (ref "U3") (pin "7") (pinfunction "V+_7") (pintype "power_in"))
      (node (ref "U4") (pin "7") (pinfunction "V+_7") (pintype "power_in"))
      (node (ref "U5") (pin "7") (pinfunction "V+_7") (pintype "power_in"))
      (node (ref "U8") (pin "1") (pinfunction "VIN_1") (pintype "input"))
      (node (ref "U8") (pin "6") (pinfunction "~{SHDN}_6") (pintype "input"))
      (node (ref "U9") (pin "1") (pinfunction "VCC_1") (pintype "power_in"))
    )
    (net (code "58") (name "unconnected-(MACHINE3-Pad2)") (class "Default")
      (node (ref "MACHINE3") (pin "2") (pinfunction "2_2") (pintype "passive"))
    )
    (net (code "59") (name "unconnected-(MACHINE3-Pad3)") (class "Default")
      (node (ref "MACHINE3") (pin "3") (pinfunction "3_3") (pintype "passive"))
    )
    (net (code "60") (name "unconnected-(X1-GND-PadGND@5)") (class "Default")
      (node (ref "X1") (pin "GND@5") (pinfunction "GND_GND@5") (pintype "bidirectional"))
    )
    (net (code "61") (name "unconnected-(X1-Pad3V3_EN)") (class "Default")
      (node (ref "X1") (pin "3V3_EN") (pinfunction "3V3_EN_3V3_EN") (pintype "bidirectional"))
    )
    (net (code "62") (name "unconnected-(X1-PadADC_VREF)") (class "Default")
      (node (ref "X1") (pin "ADC_VREF") (pinfunction "ADC_VREF_ADC_VREF") (pintype "bidirectional"))
    )
    (net (code "63") (name "unconnected-(X1-PadGP3)") (class "Default")
      (node (ref "X1") (pin "GP3") (pinfunction "GP3_GP3") (pintype "bidirectional"))
    )
    (net (code "64") (name "unconnected-(X1-PadGP7)") (class "Default")
      (node (ref "X1") (pin "GP7") (pinfunction "GP7_GP7") (pintype "bidirectional"))
    )
    (net (code "65") (name "unconnected-(X1-PadGP8)") (class "Default")
      (node (ref "X1") (pin "GP8") (pinfunction "GP8_GP8") (pintype "bidirectional"))
    )
    (net (code "66") (name "unconnected-(X1-PadGP9)") (class "Default")
      (node (ref "X1") (pin "GP9") (pinfunction "GP9_GP9") (pintype "bidirectional"))
    )
    (net (code "67") (name "unconnected-(X1-PadGP10)") (class "Default")
      (node (ref "X1") (pin "GP10") (pinfunction "GP10_GP10") (pintype "bidirectional"))
    )
    (net (code "68") (name "unconnected-(X1-PadGP11)") (class "Default")
      (node (ref "X1") (pin "GP11") (pinfunction "GP11_GP11") (pintype "bidirectional"))
    )
    (net (code "69") (name "unconnected-(X1-PadGP12)") (class "Default")
      (node (ref "X1") (pin "GP12") (pinfunction "GP12_GP12") (pintype "bidirectional"))
    )
    (net (code "70") (name "unconnected-(X1-PadGP13)") (class "Default")
      (node (ref "X1") (pin "GP13") (pinfunction "GP13_GP13") (pintype "bidirectional"))
    )
    (net (code "71") (name "unconnected-(X1-PadGP14)") (class "Default")
      (node (ref "X1") (pin "GP14") (pinfunction "GP14_GP14") (pintype "bidirectional"))
    )
    (net (code "72") (name "unconnected-(X1-PadGP15)") (class "Default")
      (node (ref "X1") (pin "GP15") (pinfunction "GP15_GP15") (pintype "bidirectional"))
    )
    (net (code "73") (name "unconnected-(X1-PadGP16)") (class "Default")
      (node (ref "X1") (pin "GP16") (pinfunction "GP16_GP16") (pintype "bidirectional"))
    )
    (net (code "74") (name "unconnected-(X1-PadGP22)") (class "Default")
      (node (ref "X1") (pin "GP22") (pinfunction "GP22_GP22") (pintype "bidirectional"))
    )
    (net (code "75") (name "unconnected-(X1-PadGP28_A2)") (class "Default")
      (node (ref "X1") (pin "GP28_A2") (pinfunction "GP28_A2_GP28_A2") (pintype "bidirectional"))
    )
    (net (code "76") (name "unconnected-(X1-PadRUN)") (class "Default")
      (node (ref "X1") (pin "RUN") (pinfunction "RUN_RUN") (pintype "bidirectional"))
    )
    (net (code "77") (name "unconnected-(X1-PadSWCLK)") (class "Default")
      (node (ref "X1") (pin "SWCLK") (pinfunction "SWCLK_SWCLK") (pintype "bidirectional"))
    )
    (net (code "78") (name "unconnected-(X1-PadSWDIO)") (class "Default")
      (node (ref "X1") (pin "SWDIO") (pinfunction "SWDIO_SWDIO") (pintype "bidirectional"))
    )
    (net (code "79") (name "unconnected-(X1-PadVBUS)") (class "Default")
      (node (ref "X1") (pin "VBUS") (pinfunction "VBUS_VBUS") (pintype "bidirectional"))
    )
  )
)
